# SimpleFMCWRadar-RFBoard.net
KiCad netlist of a schematic drawn in EAGLE
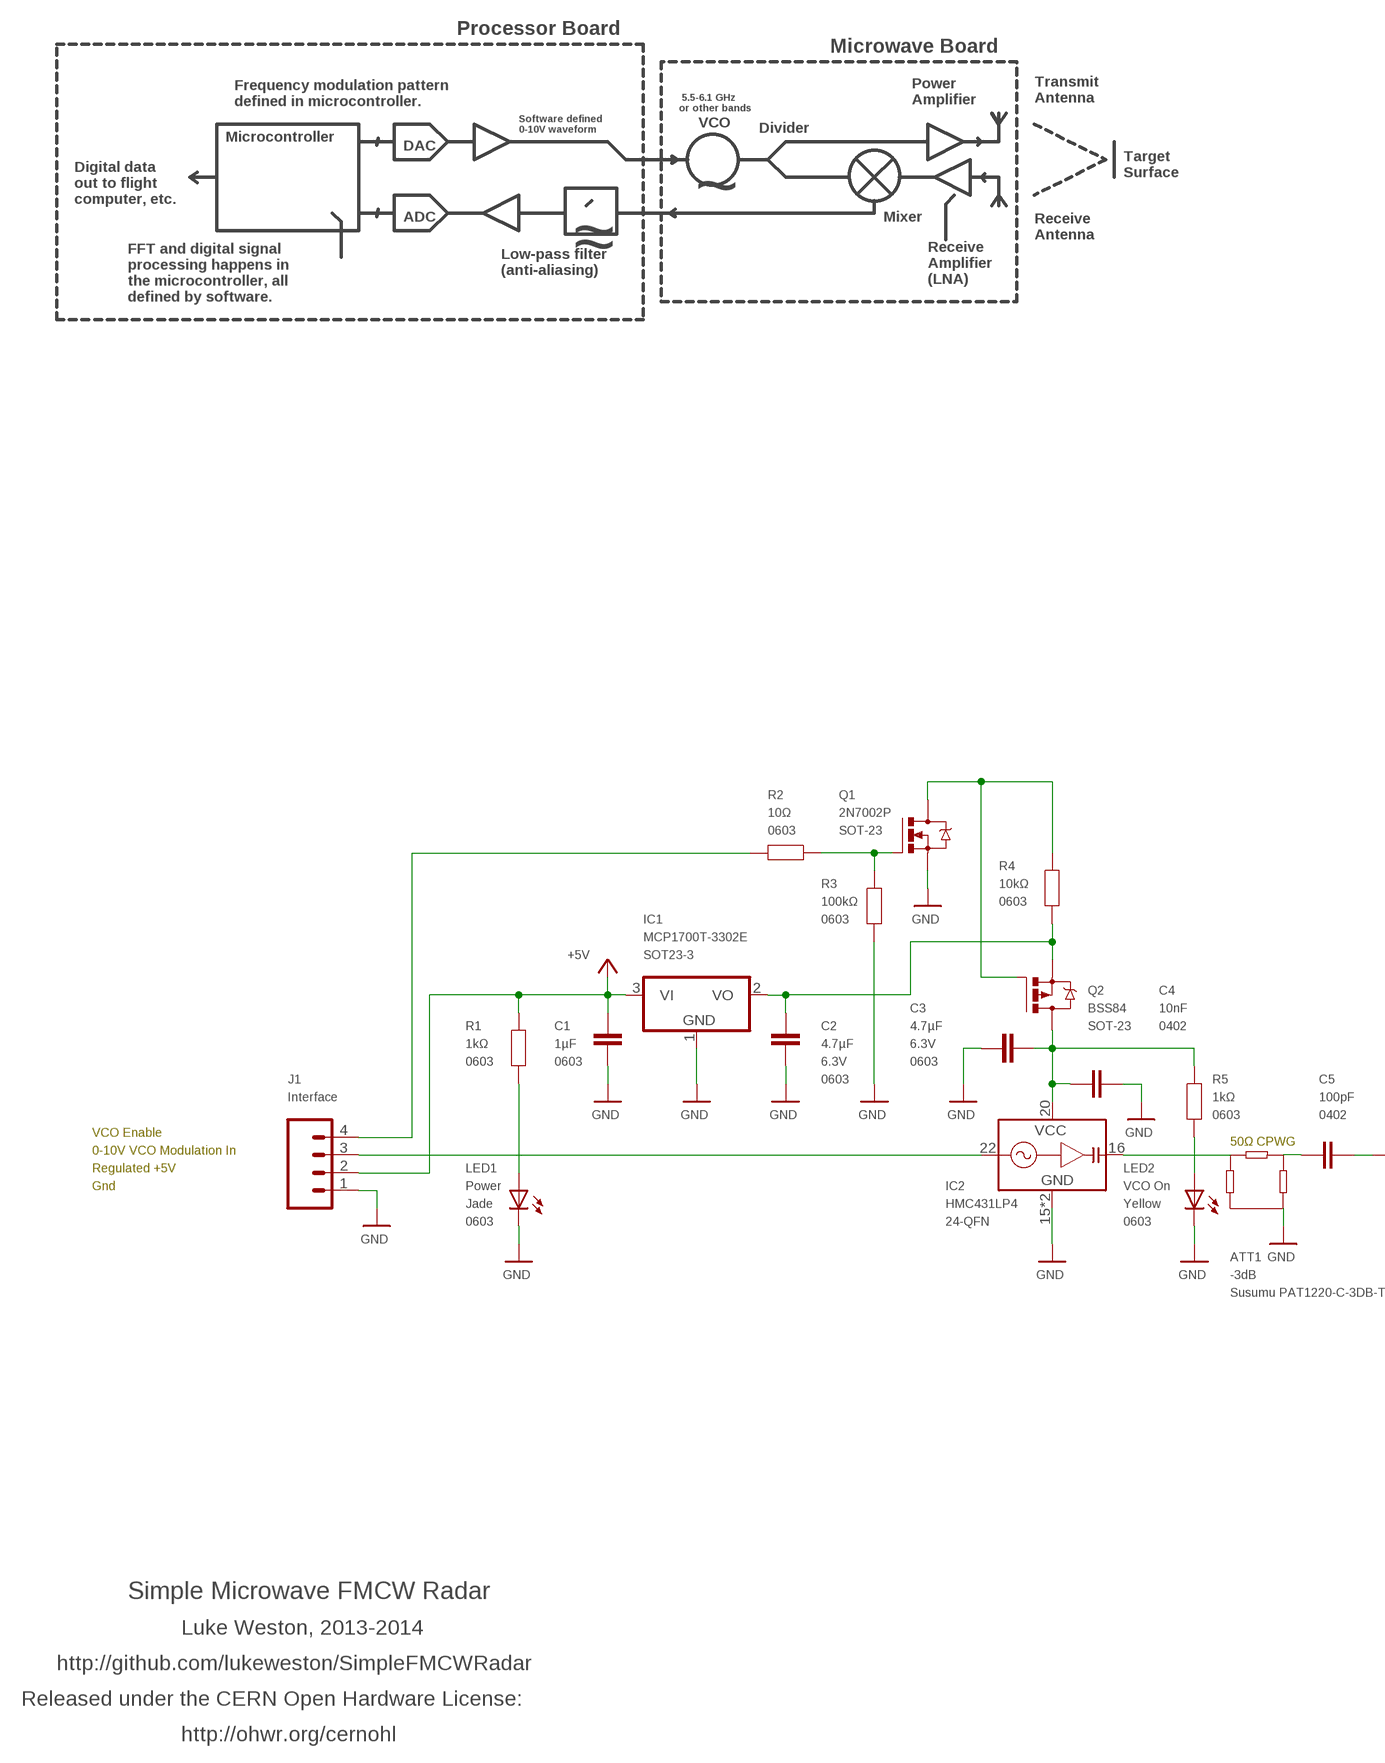
[diagram p0: schematic, sheet 1, part 1 of 2]
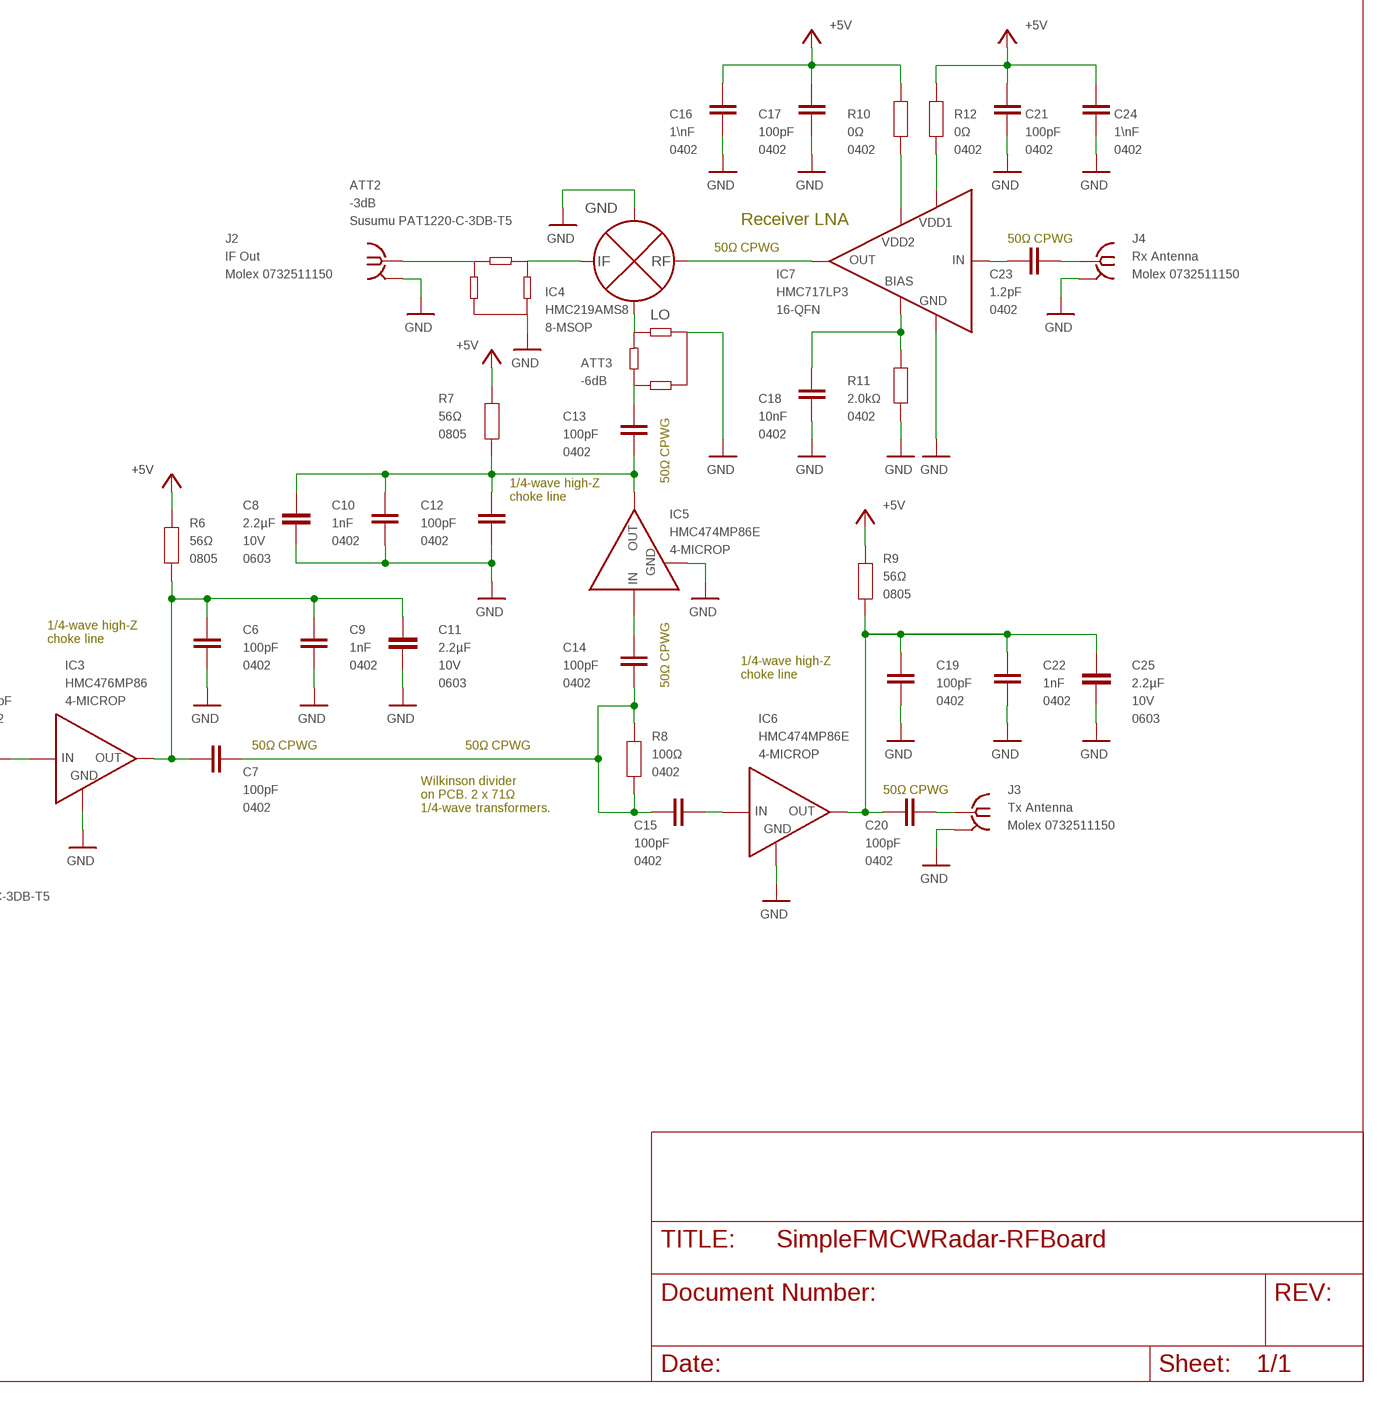
[diagram p1: schematic, sheet 1, part 2 of 2]

(export (version "E")
  (design (tool "Eeschema 10.0.6"))
  (components
    (comp (ref "ATT1")
      (value "-3dB")
      (footprint "eagle-import:PAT1220")
      (fields (field (name "ID") "Susumu PAT1220-C-3DB-T5"))
      (libsource (lib "eagle-import") (part "PAT1220"))
    )
    (comp (ref "ATT2")
      (value "-3dB")
      (footprint "eagle-import:PAT1220")
      (fields (field (name "ID") "Susumu PAT1220-C-3DB-T5"))
      (libsource (lib "eagle-import") (part "PAT1220"))
    )
    (comp (ref "ATT3")
      (value "-6dB")
      (footprint "eagle-import:PAT1220")
      (libsource (lib "eagle-import") (part "PAT1220"))
    )
    (comp (ref "C1")
      (value "1µF")
      (footprint "eagle-import:0603")
      (fields (field (name "PACKAGE") "0603"))
      (libsource (lib "eagle-import") (part "CAP0603"))
    )
    (comp (ref "C2")
      (value "4.7µF")
      (footprint "eagle-import:0603")
      (fields (field (name "PACKAGE") "0603") (field (name "VOLTAGE") "6.3V"))
      (libsource (lib "eagle-import") (part "CAP0603"))
    )
    (comp (ref "C3")
      (value "4.7µF")
      (footprint "eagle-import:0603")
      (fields (field (name "PACKAGE") "0603") (field (name "VOLTAGE") "6.3V"))
      (libsource (lib "eagle-import") (part "CAP0603"))
    )
    (comp (ref "C4")
      (value "10nF")
      (footprint "eagle-import:0402")
      (fields (field (name "PACKAGE") "0402"))
      (libsource (lib "eagle-import") (part "CAPACITOR0402"))
    )
    (comp (ref "C5")
      (value "100pF")
      (footprint "eagle-import:0402")
      (fields (field (name "PACKAGE") "0402"))
      (libsource (lib "eagle-import") (part "CAPACITOR0402"))
    )
    (comp (ref "C6")
      (value "100pF")
      (footprint "eagle-import:0402")
      (fields (field (name "PACKAGE") "0402"))
      (libsource (lib "eagle-import") (part "CAPACITOR0402"))
    )
    (comp (ref "C7")
      (value "100pF")
      (footprint "eagle-import:0402")
      (fields (field (name "PACKAGE") "0402"))
      (libsource (lib "eagle-import") (part "CAPACITOR0402"))
    )
    (comp (ref "C8")
      (value "2.2µF")
      (footprint "eagle-import:0603")
      (fields (field (name "PACKAGE") "0603") (field (name "VOLTAGE") "10V"))
      (libsource (lib "eagle-import") (part "CAP0603"))
    )
    (comp (ref "C9")
      (value "1nF")
      (footprint "eagle-import:0402")
      (fields (field (name "PACKAGE") "0402"))
      (libsource (lib "eagle-import") (part "CAPACITOR0402"))
    )
    (comp (ref "C10")
      (value "1nF")
      (footprint "eagle-import:0402")
      (fields (field (name "PACKAGE") "0402"))
      (libsource (lib "eagle-import") (part "CAPACITOR0402"))
    )
    (comp (ref "C11")
      (value "2.2µF")
      (footprint "eagle-import:0603")
      (fields (field (name "PACKAGE") "0603") (field (name "VOLTAGE") "10V"))
      (libsource (lib "eagle-import") (part "CAP0603"))
    )
    (comp (ref "C12")
      (value "100pF")
      (footprint "eagle-import:0402")
      (fields (field (name "PACKAGE") "0402"))
      (libsource (lib "eagle-import") (part "CAPACITOR0402"))
    )
    (comp (ref "C13")
      (value "100pF")
      (footprint "eagle-import:0402")
      (fields (field (name "PACKAGE") "0402"))
      (libsource (lib "eagle-import") (part "CAPACITOR0402"))
    )
    (comp (ref "C14")
      (value "100pF")
      (footprint "eagle-import:0402")
      (fields (field (name "PACKAGE") "0402"))
      (libsource (lib "eagle-import") (part "CAPACITOR0402"))
    )
    (comp (ref "C15")
      (value "100pF")
      (footprint "eagle-import:0402")
      (fields (field (name "PACKAGE") "0402"))
      (libsource (lib "eagle-import") (part "CAPACITOR0402"))
    )
    (comp (ref "C16")
      (value "1\\nF")
      (footprint "eagle-import:0402")
      (fields (field (name "PACKAGE") "0402"))
      (libsource (lib "eagle-import") (part "CAPACITOR0402"))
    )
    (comp (ref "C17")
      (value "100pF")
      (footprint "eagle-import:0402")
      (fields (field (name "PACKAGE") "0402"))
      (libsource (lib "eagle-import") (part "CAPACITOR0402"))
    )
    (comp (ref "C18")
      (value "10nF")
      (footprint "eagle-import:0402")
      (fields (field (name "PACKAGE") "0402"))
      (libsource (lib "eagle-import") (part "CAPACITOR0402"))
    )
    (comp (ref "C19")
      (value "100pF")
      (footprint "eagle-import:0402")
      (fields (field (name "PACKAGE") "0402"))
      (libsource (lib "eagle-import") (part "CAPACITOR0402"))
    )
    (comp (ref "C20")
      (value "100pF")
      (footprint "eagle-import:0402")
      (fields (field (name "PACKAGE") "0402"))
      (libsource (lib "eagle-import") (part "CAPACITOR0402"))
    )
    (comp (ref "C21")
      (value "100pF")
      (footprint "eagle-import:0402")
      (fields (field (name "PACKAGE") "0402"))
      (libsource (lib "eagle-import") (part "CAPACITOR0402"))
    )
    (comp (ref "C22")
      (value "1nF")
      (footprint "eagle-import:0402")
      (fields (field (name "PACKAGE") "0402"))
      (libsource (lib "eagle-import") (part "CAPACITOR0402"))
    )
    (comp (ref "C23")
      (value "1.2pF")
      (footprint "eagle-import:0402")
      (fields (field (name "PACKAGE") "0402"))
      (libsource (lib "eagle-import") (part "CAPACITOR0402"))
    )
    (comp (ref "C24")
      (value "1\\nF")
      (footprint "eagle-import:0402")
      (fields (field (name "PACKAGE") "0402"))
      (libsource (lib "eagle-import") (part "CAPACITOR0402"))
    )
    (comp (ref "C25")
      (value "2.2µF")
      (footprint "eagle-import:0603")
      (fields (field (name "PACKAGE") "0603") (field (name "VOLTAGE") "10V"))
      (libsource (lib "eagle-import") (part "CAP0603"))
    )
    (comp (ref "IC1")
      (value "MCP1700T-3302E")
      (footprint "eagle-import:SOT23")
      (fields (field (name "PACKAGE") "SOT23-3"))
      (libsource (lib "eagle-import") (part "MCP1703CB"))
    )
    (comp (ref "IC2")
      (value "HMC431LP4")
      (footprint "eagle-import:QFN24")
      (fields (field (name "PACKAGE") "24-QFN"))
      (libsource (lib "eagle-import") (part "HMC385LP4"))
    )
    (comp (ref "IC3")
      (value "HMC476MP86")
      (footprint "eagle-import:WW107")
      (fields (field (name "PACKAGE") "4-MICROP"))
      (libsource (lib "eagle-import") (part "ERA-2SM+"))
    )
    (comp (ref "IC4")
      (value "HMC219AMS8")
      (footprint "eagle-import:8-MSOP")
      (fields (field (name "PACKAGE") "8-MSOP"))
      (libsource (lib "eagle-import") (part "HMC219AMS8"))
    )
    (comp (ref "IC5")
      (value "HMC474MP86E")
      (footprint "eagle-import:WW107")
      (fields (field (name "PACKAGE") "4-MICROP"))
      (libsource (lib "eagle-import") (part "ERA-2SM+"))
    )
    (comp (ref "IC6")
      (value "HMC474MP86E")
      (footprint "eagle-import:WW107")
      (fields (field (name "PACKAGE") "4-MICROP"))
      (libsource (lib "eagle-import") (part "ERA-2SM+"))
    )
    (comp (ref "IC7")
      (value "HMC717LP3")
      (footprint "eagle-import:16-QFN")
      (fields (field (name "PACKAGE") "16-QFN"))
      (libsource (lib "eagle-import") (part "HMC717LP3"))
    )
    (comp (ref "J1")
      (value "Interface")
      (footprint "eagle-import:1X04")
      (libsource (lib "eagle-import") (part "M04PTH"))
    )
    (comp (ref "J2")
      (value "IF Out")
      (footprint "eagle-import:J502-ND-142-0701-881_886")
      (fields
        (field (name "MF") "JOHNSON COMPONENTS")
        (field (name "MPN") "142-0701-881")
        (field (name "ID") "Molex 0732511150")
        (field (name "MF_1") "JOHNSON COMPONENTS")
        (field (name "MPN_1") "142-0701-881")
        (field (name "OC_FARNELL") "1608603")
        (field (name "OC_NEWARK") "08B906")
      )
      (libsource (lib "eagle-import") (part "SMA-142-0701-881/886"))
    )
    (comp (ref "J3")
      (value "Tx Antenna")
      (footprint "eagle-import:J502-ND-142-0701-881_886")
      (fields
        (field (name "MF") "JOHNSON COMPONENTS")
        (field (name "MPN") "142-0701-881")
        (field (name "ID") "Molex 0732511150")
      )
      (libsource (lib "eagle-import") (part "SMA-142-0701-881/886"))
    )
    (comp (ref "J4")
      (value "Rx Antenna")
      (footprint "eagle-import:J502-ND-142-0701-881_886")
      (fields
        (field (name "MF") "JOHNSON COMPONENTS")
        (field (name "MPN") "142-0701-881")
        (field (name "ID") "Molex 0732511150")
      )
      (libsource (lib "eagle-import") (part "SMA-142-0701-881/886"))
    )
    (comp (ref "LED1")
      (value "Power")
      (footprint "eagle-import:LED-0603")
      (fields (field (name "COLOR") "Jade") (field (name "PACKAGE") "0603"))
      (libsource (lib "eagle-import") (part "LED0603"))
    )
    (comp (ref "LED2")
      (value "VCO On")
      (footprint "eagle-import:LED-0603")
      (fields (field (name "COLOR") "Yellow") (field (name "PACKAGE") "0603"))
      (libsource (lib "eagle-import") (part "LED0603"))
    )
    (comp (ref "Q1")
      (value "2N7002P")
      (footprint "eagle-import:SOT23-3")
      (fields (field (name "PACKAGE") "SOT-23"))
      (libsource (lib "eagle-import") (part "2N7002"))
    )
    (comp (ref "Q2")
      (value "BSS84")
      (footprint "eagle-import:SOT23-3")
      (fields (field (name "PACKAGE") "SOT-23"))
      (libsource (lib "eagle-import") (part "DMP2035U-7"))
    )
    (comp (ref "R1")
      (value "1kΩ")
      (footprint "eagle-import:0603")
      (fields (field (name "PACKAGE") "0603"))
      (libsource (lib "eagle-import") (part "RESISTOR0603"))
    )
    (comp (ref "R2")
      (value "10Ω")
      (footprint "eagle-import:0603")
      (fields (field (name "PACKAGE") "0603"))
      (libsource (lib "eagle-import") (part "RESISTOR0603"))
    )
    (comp (ref "R3")
      (value "100kΩ")
      (footprint "eagle-import:0603")
      (fields (field (name "PACKAGE") "0603"))
      (libsource (lib "eagle-import") (part "RESISTOR0603"))
    )
    (comp (ref "R4")
      (value "10kΩ")
      (footprint "eagle-import:0603")
      (fields (field (name "PACKAGE") "0603"))
      (libsource (lib "eagle-import") (part "RESISTOR0603"))
    )
    (comp (ref "R5")
      (value "1kΩ")
      (footprint "eagle-import:0603")
      (fields (field (name "PACKAGE") "0603"))
      (libsource (lib "eagle-import") (part "RESISTOR0603"))
    )
    (comp (ref "R6")
      (value "56Ω")
      (footprint "eagle-import:0805")
      (fields (field (name "PACKAGE") "0805"))
      (libsource (lib "eagle-import") (part "RESISTOR0805"))
    )
    (comp (ref "R7")
      (value "56Ω")
      (footprint "eagle-import:0805")
      (fields (field (name "PACKAGE") "0805"))
      (libsource (lib "eagle-import") (part "RESISTOR0805"))
    )
    (comp (ref "R8")
      (value "100Ω")
      (footprint "eagle-import:0402")
      (fields (field (name "PACKAGE") "0402"))
      (libsource (lib "eagle-import") (part "RESISTOR-EU0402"))
    )
    (comp (ref "R9")
      (value "56Ω")
      (footprint "eagle-import:0805")
      (fields (field (name "PACKAGE") "0805"))
      (libsource (lib "eagle-import") (part "RESISTOR0805"))
    )
    (comp (ref "R10")
      (value "0Ω")
      (footprint "eagle-import:0402")
      (fields (field (name "PACKAGE") "0402"))
      (libsource (lib "eagle-import") (part "RESISTOR-EU0402"))
    )
    (comp (ref "R11")
      (value "2.0kΩ")
      (footprint "eagle-import:0402")
      (fields (field (name "PACKAGE") "0402"))
      (libsource (lib "eagle-import") (part "RESISTOR-EU0402"))
    )
    (comp (ref "R12")
      (value "0Ω")
      (footprint "eagle-import:0402")
      (fields (field (name "PACKAGE") "0402"))
      (libsource (lib "eagle-import") (part "RESISTOR-EU0402"))
    )
  )
  (nets
    (net (code "1") (name "+5V") (class "Default")
      (node (ref "C1") (pin "2") (pinfunction "2_2") (pintype "passive"))
      (node (ref "C16") (pin "2") (pinfunction "2_2") (pintype "bidirectional"))
      (node (ref "C17") (pin "2") (pinfunction "2_2") (pintype "bidirectional"))
      (node (ref "C21") (pin "2") (pinfunction "2_2") (pintype "bidirectional"))
      (node (ref "C24") (pin "2") (pinfunction "2_2") (pintype "bidirectional"))
      (node (ref "IC1") (pin "3") (pinfunction "VI_3") (pintype "input"))
      (node (ref "J1") (pin "2") (pinfunction "2_2") (pintype "passive"))
      (node (ref "R1") (pin "2") (pinfunction "2_2") (pintype "passive"))
      (node (ref "R10") (pin "2") (pinfunction "2_2") (pintype "bidirectional"))
      (node (ref "R12") (pin "2") (pinfunction "2_2") (pintype "bidirectional"))
      (node (ref "R6") (pin "2") (pinfunction "2_2") (pintype "passive"))
      (node (ref "R7") (pin "1") (pinfunction "1_1") (pintype "passive"))
      (node (ref "R9") (pin "1") (pinfunction "1_1") (pintype "passive"))
    )
    (net (code "2") (name "GND") (class "Default")
      (node (ref "ATT1") (pin "3") (pinfunction "3_3") (pintype "bidirectional"))
      (node (ref "ATT2") (pin "3") (pinfunction "3_3") (pintype "bidirectional"))
      (node (ref "ATT3") (pin "3") (pinfunction "3_3") (pintype "bidirectional"))
      (node (ref "C1") (pin "1") (pinfunction "1_1") (pintype "passive"))
      (node (ref "C10") (pin "1") (pinfunction "1_1") (pintype "bidirectional"))
      (node (ref "C11") (pin "1") (pinfunction "1_1") (pintype "passive"))
      (node (ref "C12") (pin "1") (pinfunction "1_1") (pintype "bidirectional"))
      (node (ref "C16") (pin "1") (pinfunction "1_1") (pintype "bidirectional"))
      (node (ref "C17") (pin "1") (pinfunction "1_1") (pintype "bidirectional"))
      (node (ref "C18") (pin "1") (pinfunction "1_1") (pintype "bidirectional"))
      (node (ref "C19") (pin "2") (pinfunction "2_2") (pintype "bidirectional"))
      (node (ref "C2") (pin "2") (pinfunction "2_2") (pintype "passive"))
      (node (ref "C21") (pin "1") (pinfunction "1_1") (pintype "bidirectional"))
      (node (ref "C22") (pin "2") (pinfunction "2_2") (pintype "bidirectional"))
      (node (ref "C24") (pin "1") (pinfunction "1_1") (pintype "bidirectional"))
      (node (ref "C25") (pin "1") (pinfunction "1_1") (pintype "passive"))
      (node (ref "C3") (pin "2") (pinfunction "2_2") (pintype "passive"))
      (node (ref "C4") (pin "2") (pinfunction "2_2") (pintype "bidirectional"))
      (node (ref "C6") (pin "1") (pinfunction "1_1") (pintype "bidirectional"))
      (node (ref "C8") (pin "1") (pinfunction "1_1") (pintype "passive"))
      (node (ref "C9") (pin "1") (pinfunction "1_1") (pintype "bidirectional"))
      (node (ref "IC1") (pin "1") (pinfunction "GND_1") (pintype "passive"))
      (node (ref "IC2") (pin "15") (pinfunction "GND_15") (pintype "power_in"))
      (node (ref "IC2") (pin "EXP") (pinfunction "GND_EXP") (pintype "power_in"))
      (node (ref "IC3") (pin "2") (pinfunction "GND_2") (pintype "passive"))
      (node (ref "IC3") (pin "4") (pinfunction "GND_4") (pintype "passive"))
      (node (ref "IC4") (pin "1") (pinfunction "GND_1") (pintype "bidirectional"))
      (node (ref "IC4") (pin "3") (pinfunction "GND_3") (pintype "bidirectional"))
      (node (ref "IC4") (pin "6") (pinfunction "GND_6") (pintype "bidirectional"))
      (node (ref "IC4") (pin "8") (pinfunction "GND_8") (pintype "bidirectional"))
      (node (ref "IC5") (pin "2") (pinfunction "GND_2") (pintype "passive"))
      (node (ref "IC5") (pin "4") (pinfunction "GND_4") (pintype "passive"))
      (node (ref "IC6") (pin "2") (pinfunction "GND_2") (pintype "passive"))
      (node (ref "IC6") (pin "4") (pinfunction "GND_4") (pintype "passive"))
      (node (ref "IC7") (pin "P$1") (pinfunction "GND_P$1") (pintype "bidirectional"))
      (node (ref "IC7") (pin "P$10") (pinfunction "GND_P$10") (pintype "bidirectional"))
      (node (ref "IC7") (pin "P$12") (pinfunction "GND_P$12") (pintype "bidirectional"))
      (node (ref "IC7") (pin "P$14") (pinfunction "GND_P$14") (pintype "bidirectional"))
      (node (ref "IC7") (pin "P$16") (pinfunction "GND_P$16") (pintype "bidirectional"))
      (node (ref "IC7") (pin "P$3") (pinfunction "GND_P$3") (pintype "bidirectional"))
      (node (ref "IC7") (pin "P$4") (pinfunction "GND_P$4") (pintype "bidirectional"))
      (node (ref "IC7") (pin "P$5") (pinfunction "GND_P$5") (pintype "bidirectional"))
      (node (ref "IC7") (pin "P$6") (pinfunction "GND_P$6") (pintype "bidirectional"))
      (node (ref "IC7") (pin "P$7") (pinfunction "GND_P$7") (pintype "bidirectional"))
      (node (ref "IC7") (pin "P$9") (pinfunction "GND_P$9") (pintype "bidirectional"))
      (node (ref "IC7") (pin "PAD") (pinfunction "GND_PAD") (pintype "bidirectional"))
      (node (ref "J1") (pin "1") (pinfunction "1_1") (pintype "passive"))
      (node (ref "J2") (pin "G@1") (pinfunction "GND_G@1") (pintype "power_in"))
      (node (ref "J3") (pin "G@1") (pinfunction "GND_G@1") (pintype "power_in"))
      (node (ref "J4") (pin "G@1") (pinfunction "GND_G@1") (pintype "power_in"))
      (node (ref "LED1") (pin "C") (pinfunction "C_C") (pintype "passive"))
      (node (ref "LED2") (pin "C") (pinfunction "C_C") (pintype "passive"))
      (node (ref "Q1") (pin "2") (pinfunction "S_2") (pintype "passive"))
      (node (ref "R11") (pin "1") (pinfunction "1_1") (pintype "bidirectional"))
      (node (ref "R3") (pin "1") (pinfunction "1_1") (pintype "passive"))
    )
    (net (code "3") (name "Net-(ATT1-Pad2)") (class "Default")
      (node (ref "ATT1") (pin "2") (pinfunction "2_2") (pintype "bidirectional"))
      (node (ref "C5") (pin "1") (pinfunction "1_1") (pintype "bidirectional"))
    )
    (net (code "4") (name "Net-(ATT2-Pad1)") (class "Default")
      (node (ref "ATT2") (pin "1") (pinfunction "1_1") (pintype "bidirectional"))
      (node (ref "J2") (pin "1") (pinfunction "1_1") (pintype "passive"))
    )
    (net (code "5") (name "Net-(ATT3-Pad1)") (class "Default")
      (node (ref "ATT3") (pin "1") (pinfunction "1_1") (pintype "bidirectional"))
      (node (ref "C13") (pin "2") (pinfunction "2_2") (pintype "bidirectional"))
    )
    (net (code "6") (name "Net-(C14-Pad1)") (class "Default")
      (node (ref "C14") (pin "1") (pinfunction "1_1") (pintype "bidirectional"))
      (node (ref "C15") (pin "2") (pinfunction "2_2") (pintype "bidirectional"))
      (node (ref "C7") (pin "2") (pinfunction "2_2") (pintype "bidirectional"))
      (node (ref "R8") (pin "1") (pinfunction "1_1") (pintype "bidirectional"))
      (node (ref "R8") (pin "2") (pinfunction "2_2") (pintype "bidirectional"))
    )
    (net (code "7") (name "Net-(C20-Pad1)") (class "Default")
      (node (ref "C20") (pin "1") (pinfunction "1_1") (pintype "bidirectional"))
      (node (ref "J3") (pin "1") (pinfunction "1_1") (pintype "passive"))
    )
    (net (code "8") (name "Net-(C23-Pad1)") (class "Default")
      (node (ref "C23") (pin "1") (pinfunction "1_1") (pintype "bidirectional"))
      (node (ref "J4") (pin "1") (pinfunction "1_1") (pintype "passive"))
    )
    (net (code "9") (name "Net-(IC1-VO)") (class "Default")
      (node (ref "C2") (pin "1") (pinfunction "1_1") (pintype "passive"))
      (node (ref "IC1") (pin "2") (pinfunction "VO_2") (pintype "passive"))
      (node (ref "Q2") (pin "2") (pinfunction "S_2") (pintype "passive"))
      (node (ref "R4") (pin "1") (pinfunction "1_1") (pintype "passive"))
    )
    (net (code "10") (name "Net-(IC2-RFOUT)") (class "Default")
      (node (ref "ATT1") (pin "1") (pinfunction "1_1") (pintype "bidirectional"))
      (node (ref "IC2") (pin "16") (pinfunction "RFOUT_16") (pintype "input"))
    )
    (net (code "11") (name "Net-(IC2-VCC)") (class "Default")
      (node (ref "C3") (pin "1") (pinfunction "1_1") (pintype "passive"))
      (node (ref "C4") (pin "1") (pinfunction "1_1") (pintype "bidirectional"))
      (node (ref "IC2") (pin "20") (pinfunction "VCC_20") (pintype "power_in"))
      (node (ref "Q2") (pin "3") (pinfunction "D_3") (pintype "passive"))
      (node (ref "R5") (pin "2") (pinfunction "2_2") (pintype "passive"))
    )
    (net (code "12") (name "Net-(IC2-VTUNE)") (class "Default")
      (node (ref "IC2") (pin "22") (pinfunction "VTUNE_22") (pintype "input"))
      (node (ref "J1") (pin "3") (pinfunction "3_3") (pintype "passive"))
    )
    (net (code "13") (name "Net-(IC3-IN)") (class "Default")
      (node (ref "C5") (pin "2") (pinfunction "2_2") (pintype "bidirectional"))
      (node (ref "IC3") (pin "1") (pinfunction "IN_1") (pintype "bidirectional"))
    )
    (net (code "14") (name "Net-(IC3-OUT)") (class "Default")
      (node (ref "C11") (pin "2") (pinfunction "2_2") (pintype "passive"))
      (node (ref "C6") (pin "2") (pinfunction "2_2") (pintype "bidirectional"))
      (node (ref "C7") (pin "1") (pinfunction "1_1") (pintype "bidirectional"))
      (node (ref "C9") (pin "2") (pinfunction "2_2") (pintype "bidirectional"))
      (node (ref "IC3") (pin "3") (pinfunction "OUT_3") (pintype "bidirectional"))
      (node (ref "R6") (pin "1") (pinfunction "1_1") (pintype "passive"))
    )
    (net (code "15") (name "Net-(IC4-IF)") (class "Default")
      (node (ref "ATT2") (pin "2") (pinfunction "2_2") (pintype "bidirectional"))
      (node (ref "IC4") (pin "5") (pinfunction "IF_5") (pintype "bidirectional"))
    )
    (net (code "16") (name "Net-(IC4-LO)") (class "Default")
      (node (ref "ATT3") (pin "2") (pinfunction "2_2") (pintype "bidirectional"))
      (node (ref "IC4") (pin "2") (pinfunction "LO_2") (pintype "bidirectional"))
    )
    (net (code "17") (name "Net-(IC4-RF)") (class "Default")
      (node (ref "IC4") (pin "7") (pinfunction "RF_7") (pintype "bidirectional"))
      (node (ref "IC7") (pin "P$11") (pinfunction "OUT_P$11") (pintype "bidirectional"))
    )
    (net (code "18") (name "Net-(IC5-IN)") (class "Default")
      (node (ref "C14") (pin "2") (pinfunction "2_2") (pintype "bidirectional"))
      (node (ref "IC5") (pin "1") (pinfunction "IN_1") (pintype "bidirectional"))
    )
    (net (code "19") (name "Net-(IC5-OUT)") (class "Default")
      (node (ref "C10") (pin "2") (pinfunction "2_2") (pintype "bidirectional"))
      (node (ref "C12") (pin "2") (pinfunction "2_2") (pintype "bidirectional"))
      (node (ref "C13") (pin "1") (pinfunction "1_1") (pintype "bidirectional"))
      (node (ref "C8") (pin "2") (pinfunction "2_2") (pintype "passive"))
      (node (ref "IC5") (pin "3") (pinfunction "OUT_3") (pintype "bidirectional"))
      (node (ref "R7") (pin "2") (pinfunction "2_2") (pintype "passive"))
    )
    (net (code "20") (name "Net-(IC6-IN)") (class "Default")
      (node (ref "C15") (pin "1") (pinfunction "1_1") (pintype "bidirectional"))
      (node (ref "IC6") (pin "1") (pinfunction "IN_1") (pintype "bidirectional"))
    )
    (net (code "21") (name "Net-(IC6-OUT)") (class "Default")
      (node (ref "C19") (pin "1") (pinfunction "1_1") (pintype "bidirectional"))
      (node (ref "C20") (pin "2") (pinfunction "2_2") (pintype "bidirectional"))
      (node (ref "C22") (pin "1") (pinfunction "1_1") (pintype "bidirectional"))
      (node (ref "C25") (pin "2") (pinfunction "2_2") (pintype "passive"))
      (node (ref "IC6") (pin "3") (pinfunction "OUT_3") (pintype "bidirectional"))
      (node (ref "R9") (pin "2") (pinfunction "2_2") (pintype "passive"))
    )
    (net (code "22") (name "Net-(IC7-BIAS)") (class "Default")
      (node (ref "C18") (pin "2") (pinfunction "2_2") (pintype "bidirectional"))
      (node (ref "IC7") (pin "P$8") (pinfunction "BIAS_P$8") (pintype "bidirectional"))
      (node (ref "R11") (pin "2") (pinfunction "2_2") (pintype "bidirectional"))
    )
    (net (code "23") (name "Net-(IC7-IN)") (class "Default")
      (node (ref "C23") (pin "2") (pinfunction "2_2") (pintype "bidirectional"))
      (node (ref "IC7") (pin "P$2") (pinfunction "IN_P$2") (pintype "bidirectional"))
    )
    (net (code "24") (name "Net-(IC7-VDD1)") (class "Default")
      (node (ref "IC7") (pin "P$15") (pinfunction "VDD1_P$15") (pintype "bidirectional"))
      (node (ref "R12") (pin "1") (pinfunction "1_1") (pintype "bidirectional"))
    )
    (net (code "25") (name "Net-(IC7-VDD2)") (class "Default")
      (node (ref "IC7") (pin "P$13") (pinfunction "VDD2_P$13") (pintype "bidirectional"))
      (node (ref "R10") (pin "1") (pinfunction "1_1") (pintype "bidirectional"))
    )
    (net (code "26") (name "Net-(J1-Pad4)") (class "Default")
      (node (ref "J1") (pin "4") (pinfunction "4_4") (pintype "passive"))
      (node (ref "R2") (pin "2") (pinfunction "2_2") (pintype "passive"))
    )
    (net (code "27") (name "Net-(LED1-PadA)") (class "Default")
      (node (ref "LED1") (pin "A") (pinfunction "A_A") (pintype "passive"))
      (node (ref "R1") (pin "1") (pinfunction "1_1") (pintype "passive"))
    )
    (net (code "28") (name "Net-(LED2-PadA)") (class "Default")
      (node (ref "LED2") (pin "A") (pinfunction "A_A") (pintype "passive"))
      (node (ref "R5") (pin "1") (pinfunction "1_1") (pintype "passive"))
    )
    (net (code "29") (name "Net-(Q1-D)") (class "Default")
      (node (ref "Q1") (pin "3") (pinfunction "D_3") (pintype "passive"))
      (node (ref "Q2") (pin "1") (pinfunction "G_1") (pintype "passive"))
      (node (ref "R4") (pin "2") (pinfunction "2_2") (pintype "passive"))
    )
    (net (code "30") (name "Net-(Q1-G)") (class "Default")
      (node (ref "Q1") (pin "1") (pinfunction "G_1") (pintype "passive"))
      (node (ref "R2") (pin "1") (pinfunction "1_1") (pintype "passive"))
      (node (ref "R3") (pin "2") (pinfunction "2_2") (pintype "passive"))
    )
  )
)
